# Camera.net
KiCad netlist of a schematic drawn in Altium Designer
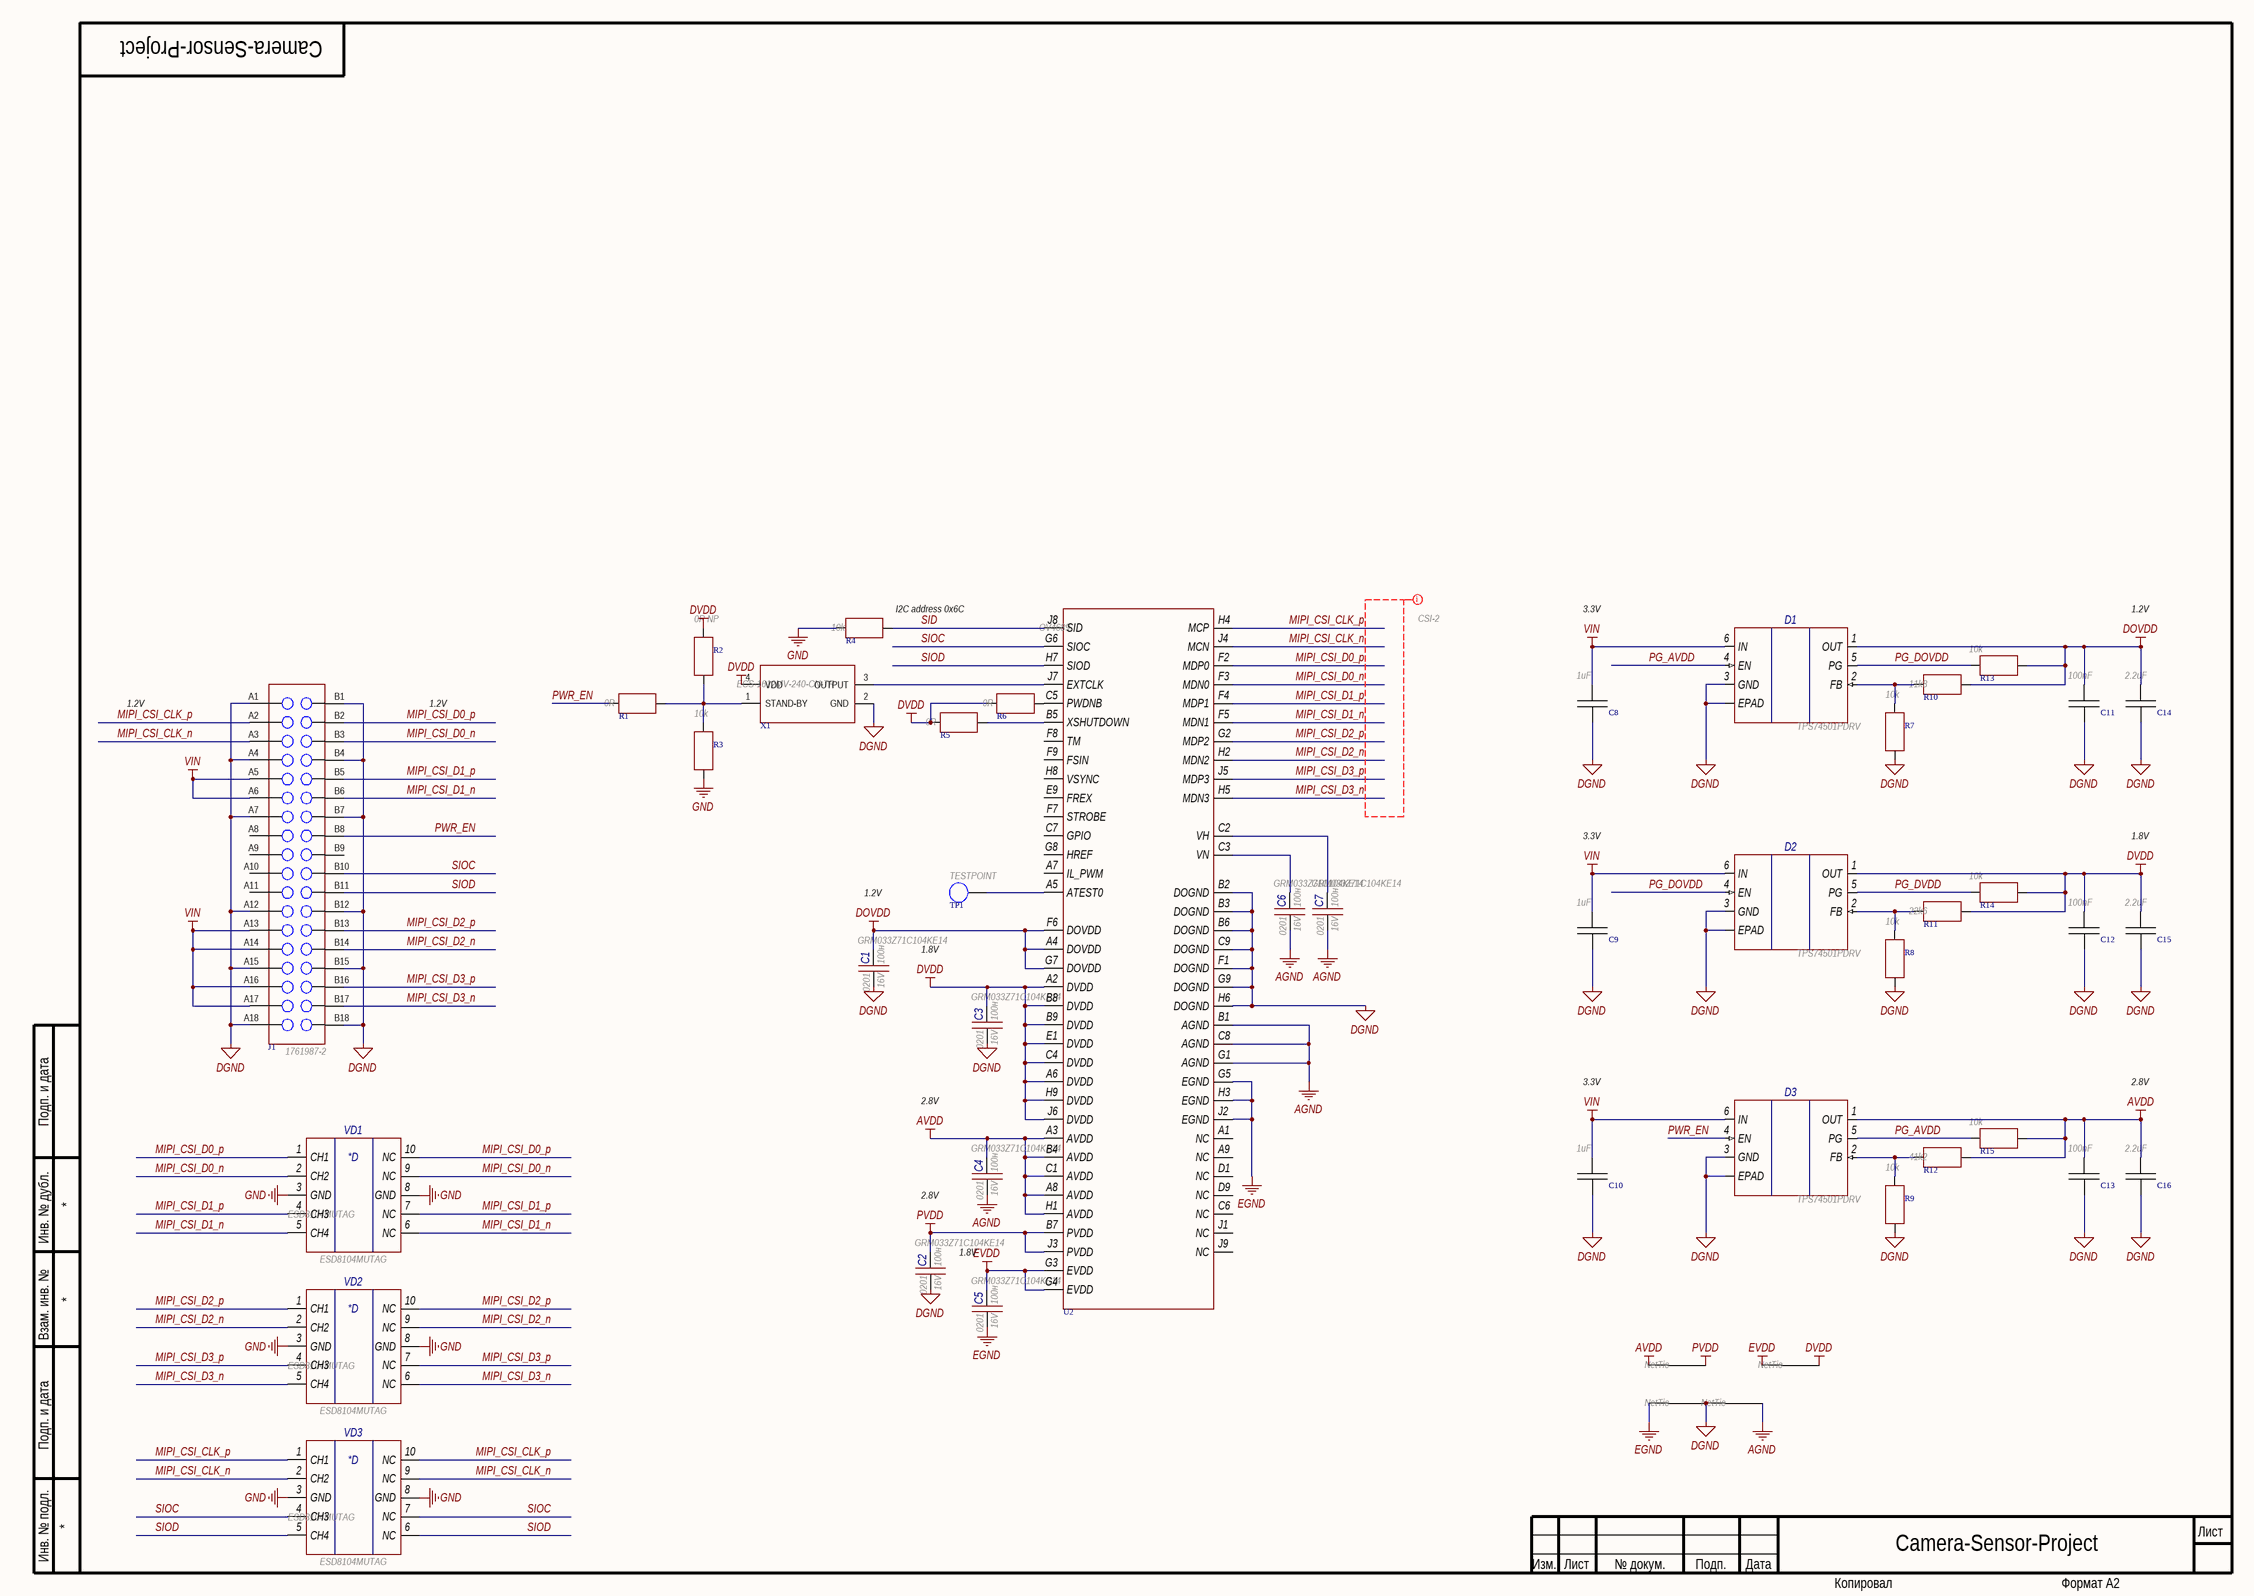
[diagram p0: Camera.SchDoc]

(export (version "E")
  (design (tool "Eeschema 10.0.6"))
  (components
    (comp (ref "C1")
      (value "GRM033Z71C104KE14")
      (footprint "CAPC_0.63x0.33x0.33Body; IPC: N; Pad Gap: 0.25")
      (fields
        (field (name "2) PACKAGE") "0201")
        (field (name "3) VOLTAGE") "16V")
        (field (name "ЗНАЧЕНИЕ") "100н")
        (field (name "MANUFACTURER") "Murata")
      )
      (libsource (lib "Concord PRO") (part "Capacitor Unpolarized"))
    )
    (comp (ref "C2")
      (value "GRM033Z71C104KE14")
      (footprint "CAPC_0.63x0.33x0.33Body; IPC: N; Pad Gap: 0.25")
      (fields
        (field (name "2) PACKAGE") "0201")
        (field (name "3) VOLTAGE") "16V")
        (field (name "ЗНАЧЕНИЕ") "100н")
        (field (name "MANUFACTURER") "Murata")
      )
      (libsource (lib "Concord PRO") (part "Capacitor Unpolarized"))
    )
    (comp (ref "C3")
      (value "GRM033Z71C104KE14")
      (footprint "CAPC_0.63x0.33x0.33Body; IPC: N; Pad Gap: 0.25")
      (fields
        (field (name "2) PACKAGE") "0201")
        (field (name "3) VOLTAGE") "16V")
        (field (name "ЗНАЧЕНИЕ") "100н")
        (field (name "MANUFACTURER") "Murata")
      )
      (libsource (lib "Concord PRO") (part "Capacitor Unpolarized"))
    )
    (comp (ref "C4")
      (value "GRM033Z71C104KE14")
      (footprint "CAPC_0.63x0.33x0.33Body; IPC: N; Pad Gap: 0.25")
      (fields
        (field (name "2) PACKAGE") "0201")
        (field (name "3) VOLTAGE") "16V")
        (field (name "ЗНАЧЕНИЕ") "100н")
        (field (name "MANUFACTURER") "Murata")
      )
      (libsource (lib "Concord PRO") (part "Capacitor Unpolarized"))
    )
    (comp (ref "C5")
      (value "GRM033Z71C104KE14")
      (footprint "CAPC_0.63x0.33x0.33Body; IPC: N; Pad Gap: 0.25")
      (fields
        (field (name "2) PACKAGE") "0201")
        (field (name "3) VOLTAGE") "16V")
        (field (name "ЗНАЧЕНИЕ") "100н")
        (field (name "MANUFACTURER") "Murata")
      )
      (libsource (lib "Concord PRO") (part "Capacitor Unpolarized"))
    )
    (comp (ref "C6")
      (value "GRM033Z71C104KE14")
      (footprint "CAPC_0.63x0.33x0.33Body; IPC: N; Pad Gap: 0.25")
      (fields
        (field (name "2) PACKAGE") "0201")
        (field (name "3) VOLTAGE") "16V")
        (field (name "ЗНАЧЕНИЕ") "100н")
        (field (name "MANUFACTURER") "Murata")
      )
      (libsource (lib "Concord PRO") (part "Capacitor Unpolarized"))
    )
    (comp (ref "C7")
      (value "GRM033Z71C104KE14")
      (footprint "CAPC_0.63x0.33x0.33Body; IPC: N; Pad Gap: 0.25")
      (fields
        (field (name "2) PACKAGE") "0201")
        (field (name "3) VOLTAGE") "16V")
        (field (name "ЗНАЧЕНИЕ") "100н")
        (field (name "MANUFACTURER") "Murata")
      )
      (libsource (lib "Concord PRO") (part "Capacitor Unpolarized"))
    )
    (comp (ref "C8")
      (value "1uF")
      (footprint "PcbLib:C0603")
      (fields
        (field (name "PART NUMBER") "CL10B105KO8NNNC")
        (field (name "TOLERANCE") "10%")
        (field (name "VOLTAGE") "16V")
      )
      (libsource (lib "Capacitor") (part "Cap 1uF 10% 16V_Samsung"))
    )
    (comp (ref "C9")
      (value "1uF")
      (footprint "PcbLib:C0603")
      (fields
        (field (name "PART NUMBER") "CL10B105KO8NNNC")
        (field (name "TOLERANCE") "10%")
        (field (name "VOLTAGE") "16V")
      )
      (libsource (lib "Capacitor") (part "Cap 1uF 10% 16V_Samsung"))
    )
    (comp (ref "C10")
      (value "1uF")
      (footprint "PcbLib:C0603")
      (fields
        (field (name "PART NUMBER") "CL10B105KO8NNNC")
        (field (name "TOLERANCE") "10%")
        (field (name "VOLTAGE") "16V")
      )
      (libsource (lib "Capacitor") (part "Cap 1uF 10% 16V_Samsung"))
    )
    (comp (ref "C11")
      (value "100nF")
      (footprint "PcbLib:C0603")
      (fields
        (field (name "PART NUMBER") "06033G104ZAT2A")
        (field (name "TOLERANCE") "+80% -20%")
        (field (name "VOLTAGE") "25V")
      )
      (libsource (lib "Capacitor") (part "Cap 100nF 20% 25V"))
    )
    (comp (ref "C12")
      (value "100nF")
      (footprint "PcbLib:C0603")
      (fields
        (field (name "PART NUMBER") "06033G104ZAT2A")
        (field (name "TOLERANCE") "+80% -20%")
        (field (name "VOLTAGE") "25V")
      )
      (libsource (lib "Capacitor") (part "Cap 100nF 20% 25V"))
    )
    (comp (ref "C13")
      (value "100nF")
      (footprint "PcbLib:C0603")
      (fields
        (field (name "PART NUMBER") "06033G104ZAT2A")
        (field (name "TOLERANCE") "+80% -20%")
        (field (name "VOLTAGE") "25V")
      )
      (libsource (lib "Capacitor") (part "Cap 100nF 20% 25V"))
    )
    (comp (ref "C14")
      (value "2.2uF")
      (footprint "PcbLib:C0603")
      (fields
        (field (name "PART NUMBER") "06036D225KAT2A")
        (field (name "TOLERANCE") "10%")
        (field (name "VOLTAGE") "6.3V")
      )
      (libsource (lib "Capacitor") (part "Cap 2.2uF 10% 6.3V"))
    )
    (comp (ref "C15")
      (value "2.2uF")
      (footprint "PcbLib:C0603")
      (fields
        (field (name "PART NUMBER") "06036D225KAT2A")
        (field (name "TOLERANCE") "10%")
        (field (name "VOLTAGE") "6.3V")
      )
      (libsource (lib "Capacitor") (part "Cap 2.2uF 10% 6.3V"))
    )
    (comp (ref "C16")
      (value "2.2uF")
      (footprint "PcbLib:C0603")
      (fields
        (field (name "PART NUMBER") "06036D225KAT2A")
        (field (name "TOLERANCE") "10%")
        (field (name "VOLTAGE") "6.3V")
      )
      (libsource (lib "Capacitor") (part "Cap 2.2uF 10% 6.3V"))
    )
    (comp (ref "D1")
      (value "TPS74501PDRV")
      (footprint "WSON6_2.1x2.1x0.8Body; Recommended: Texas Instruments")
      (description "IC REG LIN POS ADJ 500MA 6WSON")
      (fields (field (name "MANUFACTURER") "Texas Instruments"))
      (libsource (lib "Concord PRO") (part "TPS74501PDRV"))
    )
    (comp (ref "D2")
      (value "TPS74501PDRV")
      (footprint "WSON6_2.1x2.1x0.8Body; Recommended: Texas Instruments")
      (description "IC REG LIN POS ADJ 500MA 6WSON")
      (fields (field (name "MANUFACTURER") "Texas Instruments"))
      (libsource (lib "Concord PRO") (part "TPS74501PDRV"))
    )
    (comp (ref "D3")
      (value "TPS74501PDRV")
      (footprint "WSON6_2.1x2.1x0.8Body; Recommended: Texas Instruments")
      (description "IC REG LIN POS ADJ 500MA 6WSON")
      (fields (field (name "MANUFACTURER") "Texas Instruments"))
      (libsource (lib "Concord PRO") (part "TPS74501PDRV"))
    )
    (comp (ref "J1")
      (value "1761987-2")
      (footprint "CON: 36_1761987-2_TEC")
      (description "CONN MINI SAS RCP 36P SLD RA SMD")
      (libsource (lib "Connector") (part "1761987-2"))
    )
    (comp (ref "JT1")
      (value "NetTie")
      (footprint "CON: nettie_0.8")
      (libsource (lib "Other") (part "NetTie"))
    )
    (comp (ref "JT2")
      (value "NetTie")
      (footprint "CON: nettie_0.8")
      (libsource (lib "Other") (part "NetTie"))
    )
    (comp (ref "JT3")
      (value "NetTie")
      (footprint "CON: nettie_0.8")
      (libsource (lib "Other") (part "NetTie"))
    )
    (comp (ref "JT4")
      (value "NetTie")
      (footprint "CON: nettie_0.8")
      (libsource (lib "Other") (part "NetTie"))
    )
    (comp (ref "R1")
      (value "0R")
      (footprint "PcbLib:R0603")
      (fields (field (name "PART NUMBER") "P0.0GDKR-ND") (field (name "TOLERANCE") "5%"))
      (libsource (lib "Resistor") (part "Res 0R OHM 0603"))
    )
    (comp (ref "R2")
      (value "0R NP")
      (footprint "PcbLib:R0603")
      (fields (field (name "TOLERANCE") "1%"))
      (libsource (lib "Resistor") (part "Res 0R NP 1% 0603"))
    )
    (comp (ref "R3")
      (value "10k")
      (footprint "PcbLib:R0603")
      (fields (field (name "PART NUMBER") "P10.0KHTR-ND") (field (name "TOLERANCE") "1%"))
      (libsource (lib "Resistor") (part "Res 10k 1% 0603"))
    )
    (comp (ref "R4")
      (value "10k")
      (footprint "PcbLib:R0603")
      (fields (field (name "PART NUMBER") "P10.0KHTR-ND") (field (name "TOLERANCE") "1%"))
      (libsource (lib "") (part "Res 10k 1% 0603_2"))
    )
    (comp (ref "R5")
      (value "0R")
      (footprint "PcbLib:R0603")
      (fields (field (name "PART NUMBER") "P0.0GDKR-ND") (field (name "TOLERANCE") "5%"))
      (libsource (lib "Resistor") (part "Res 0R OHM 0603"))
    )
    (comp (ref "R6")
      (value "0R")
      (footprint "PcbLib:R0603")
      (fields (field (name "PART NUMBER") "P0.0GDKR-ND") (field (name "TOLERANCE") "5%"))
      (libsource (lib "Resistor") (part "Res 0R OHM 0603"))
    )
    (comp (ref "R7")
      (value "10k")
      (footprint "PcbLib:R0603")
      (fields (field (name "PART NUMBER") "P10.0KHTR-ND") (field (name "TOLERANCE") "1%"))
      (libsource (lib "Resistor") (part "Res 10k 1% 0603"))
    )
    (comp (ref "R8")
      (value "10k")
      (footprint "PcbLib:R0603")
      (fields (field (name "PART NUMBER") "P10.0KHTR-ND") (field (name "TOLERANCE") "1%"))
      (libsource (lib "Resistor") (part "Res 10k 1% 0603"))
    )
    (comp (ref "R9")
      (value "10k")
      (footprint "PcbLib:R0603")
      (fields (field (name "PART NUMBER") "P10.0KHTR-ND") (field (name "TOLERANCE") "1%"))
      (libsource (lib "Resistor") (part "Res 10k 1% 0603"))
    )
    (comp (ref "R10")
      (value "11k8")
      (footprint "PcbLib:R0603")
      (fields (field (name "TOLERANCE") "1%"))
      (libsource (lib "Resistor") (part "Res 11k8 1% 0603"))
    )
    (comp (ref "R11")
      (value "22k6")
      (footprint "PcbLib:R0603")
      (fields (field (name "TOLERANCE") "1%"))
      (libsource (lib "Resistor") (part "Res 22k6 1% 0603"))
    )
    (comp (ref "R12")
      (value "41k2")
      (footprint "PcbLib:R0603")
      (fields (field (name "TOLERANCE") "1%"))
      (libsource (lib "Resistor") (part "Res 41k2 1% 0603"))
    )
    (comp (ref "R13")
      (value "10k")
      (footprint "PcbLib:R0603")
      (fields (field (name "PART NUMBER") "P10.0KHTR-ND") (field (name "TOLERANCE") "1%"))
      (libsource (lib "") (part "Res 10k 1% 0603_1"))
    )
    (comp (ref "R14")
      (value "10k")
      (footprint "PcbLib:R0603")
      (fields (field (name "PART NUMBER") "P10.0KHTR-ND") (field (name "TOLERANCE") "1%"))
      (libsource (lib "") (part "Res 10k 1% 0603_1"))
    )
    (comp (ref "R15")
      (value "10k")
      (footprint "PcbLib:R0603")
      (fields (field (name "PART NUMBER") "P10.0KHTR-ND") (field (name "TOLERANCE") "1%"))
      (libsource (lib "") (part "Res 10k 1% 0603_1"))
    )
    (comp (ref "TP1")
      (value "TESTPOINT")
      (footprint "PcbLib:TP")
      (libsource (lib "Other") (part "TESTPOINT"))
    )
    (comp (ref "U2")
      (value "OV4689")
      (footprint "81-BGA-OMNIVISION4669")
      (description "IMAGE SENSOR 4MP 1/3 CIS SO81-BGA")
      (libsource (lib "IC") (part "OV4689"))
    )
    (comp (ref "VD1")
      (value "ESD8104MUTAG")
      (footprint "UDFN10_1.0x2.5x0.55Body; Recommended: onsemi")
      (fields (field (name "PART NUMBER") "ESD8104MUTAG") (field (name "MANUFACTURER") "onsemi"))
      (libsource (lib "Concord PRO") (part "TVS; Unidirectional Channels{colon} 4; Pinout{colon} 1, 2, 4, 5 - channels, 3, 8 - GND, 6, 7, 9, 10 - NC"))
    )
    (comp (ref "VD2")
      (value "ESD8104MUTAG")
      (footprint "UDFN10_1.0x2.5x0.55Body; Recommended: onsemi")
      (fields (field (name "PART NUMBER") "ESD8104MUTAG") (field (name "MANUFACTURER") "onsemi"))
      (libsource (lib "Concord PRO") (part "TVS; Unidirectional Channels{colon} 4; Pinout{colon} 1, 2, 4, 5 - channels, 3, 8 - GND, 6, 7, 9, 10 - NC"))
    )
    (comp (ref "VD3")
      (value "ESD8104MUTAG")
      (footprint "UDFN10_1.0x2.5x0.55Body; Recommended: onsemi")
      (fields (field (name "PART NUMBER") "ESD8104MUTAG") (field (name "MANUFACTURER") "onsemi"))
      (libsource (lib "Concord PRO") (part "TVS; Unidirectional Channels{colon} 4; Pinout{colon} 1, 2, 4, 5 - channels, 3, 8 - GND, 6, 7, 9, 10 - NC"))
    )
    (comp (ref "X1")
      (value "ECS-1612MV-240-CN-TR")
      (footprint "DFN1.6X1.2")
      (description "XTAL OSC XO 24.0000MHZ CMOS SMD")
      (libsource (lib "Synchronization") (part "ECS-1612MV-240-CN-TR"))
    )
  )
  (nets
    (net (code "1") (name "/MIPI_CSI_CLK_n") (class "Default")
      (node (ref "J1") (pin "A3") (pinfunction "A3_A3") (pintype "passive"))
      (node (ref "U2") (pin "J4") (pinfunction "MCN_J4") (pintype "passive"))
      (node (ref "VD3") (pin "2") (pinfunction "CH2_2") (pintype "passive"))
      (node (ref "VD3") (pin "9") (pinfunction "NC_9") (pintype "passive"))
    )
    (net (code "2") (name "/MIPI_CSI_CLK_p") (class "Default")
      (node (ref "J1") (pin "A2") (pinfunction "A2_A2") (pintype "passive"))
      (node (ref "U2") (pin "H4") (pinfunction "MCP_H4") (pintype "passive"))
      (node (ref "VD3") (pin "1") (pinfunction "CH1_1") (pintype "passive"))
      (node (ref "VD3") (pin "10") (pinfunction "NC_10") (pintype "passive"))
    )
    (net (code "3") (name "/MIPI_CSI_D0_n") (class "Default")
      (node (ref "J1") (pin "B3") (pinfunction "B3_B3") (pintype "passive"))
      (node (ref "U2") (pin "F3") (pinfunction "MDN0_F3") (pintype "passive"))
      (node (ref "VD1") (pin "2") (pinfunction "CH2_2") (pintype "passive"))
      (node (ref "VD1") (pin "9") (pinfunction "NC_9") (pintype "passive"))
    )
    (net (code "4") (name "/MIPI_CSI_D0_p") (class "Default")
      (node (ref "J1") (pin "B2") (pinfunction "B2_B2") (pintype "passive"))
      (node (ref "U2") (pin "F2") (pinfunction "MDP0_F2") (pintype "passive"))
      (node (ref "VD1") (pin "1") (pinfunction "CH1_1") (pintype "passive"))
      (node (ref "VD1") (pin "10") (pinfunction "NC_10") (pintype "passive"))
    )
    (net (code "5") (name "/MIPI_CSI_D1_n") (class "Default")
      (node (ref "J1") (pin "B6") (pinfunction "B6_B6") (pintype "passive"))
      (node (ref "U2") (pin "F5") (pinfunction "MDN1_F5") (pintype "passive"))
      (node (ref "VD1") (pin "5") (pinfunction "CH4_5") (pintype "passive"))
      (node (ref "VD1") (pin "6") (pinfunction "NC_6") (pintype "passive"))
    )
    (net (code "6") (name "/MIPI_CSI_D1_p") (class "Default")
      (node (ref "J1") (pin "B5") (pinfunction "B5_B5") (pintype "passive"))
      (node (ref "U2") (pin "F4") (pinfunction "MDP1_F4") (pintype "passive"))
      (node (ref "VD1") (pin "4") (pinfunction "CH3_4") (pintype "passive"))
      (node (ref "VD1") (pin "7") (pinfunction "NC_7") (pintype "passive"))
    )
    (net (code "7") (name "/MIPI_CSI_D2_n") (class "Default")
      (node (ref "J1") (pin "B14") (pinfunction "B14_B14") (pintype "passive"))
      (node (ref "U2") (pin "H2") (pinfunction "MDN2_H2") (pintype "passive"))
      (node (ref "VD2") (pin "2") (pinfunction "CH2_2") (pintype "passive"))
      (node (ref "VD2") (pin "9") (pinfunction "NC_9") (pintype "passive"))
    )
    (net (code "8") (name "/MIPI_CSI_D2_p") (class "Default")
      (node (ref "J1") (pin "B13") (pinfunction "B13_B13") (pintype "passive"))
      (node (ref "U2") (pin "G2") (pinfunction "MDP2_G2") (pintype "passive"))
      (node (ref "VD2") (pin "1") (pinfunction "CH1_1") (pintype "passive"))
      (node (ref "VD2") (pin "10") (pinfunction "NC_10") (pintype "passive"))
    )
    (net (code "9") (name "/MIPI_CSI_D3_n") (class "Default")
      (node (ref "J1") (pin "B17") (pinfunction "B17_B17") (pintype "passive"))
      (node (ref "U2") (pin "H5") (pinfunction "MDN3_H5") (pintype "passive"))
      (node (ref "VD2") (pin "5") (pinfunction "CH4_5") (pintype "passive"))
      (node (ref "VD2") (pin "6") (pinfunction "NC_6") (pintype "passive"))
    )
    (net (code "10") (name "/MIPI_CSI_D3_p") (class "Default")
      (node (ref "J1") (pin "B16") (pinfunction "B16_B16") (pintype "passive"))
      (node (ref "U2") (pin "J5") (pinfunction "MDP3_J5") (pintype "passive"))
      (node (ref "VD2") (pin "4") (pinfunction "CH3_4") (pintype "passive"))
      (node (ref "VD2") (pin "7") (pinfunction "NC_7") (pintype "passive"))
    )
    (net (code "11") (name "/PG_AVDD") (class "Default")
      (node (ref "D1") (pin "4") (pinfunction "EN_4") (pintype "input"))
      (node (ref "D3") (pin "5") (pinfunction "PG_5") (pintype "open_collector"))
      (node (ref "R15") (pin "2") (pintype "power_in"))
    )
    (net (code "12") (name "/PG_DOVDD") (class "Default")
      (node (ref "D1") (pin "5") (pinfunction "PG_5") (pintype "open_collector"))
      (node (ref "D2") (pin "4") (pinfunction "EN_4") (pintype "input"))
      (node (ref "R13") (pin "2") (pintype "power_in"))
    )
    (net (code "13") (name "/PG_DVDD") (class "Default")
      (node (ref "D2") (pin "5") (pinfunction "PG_5") (pintype "open_collector"))
      (node (ref "R14") (pin "2") (pintype "power_in"))
    )
    (net (code "14") (name "/PWR_EN") (class "Default")
      (node (ref "D3") (pin "4") (pinfunction "EN_4") (pintype "input"))
      (node (ref "J1") (pin "B8") (pinfunction "B8_B8") (pintype "passive"))
      (node (ref "R1") (pin "1") (pintype "power_in"))
    )
    (net (code "15") (name "/SID") (class "Default")
      (node (ref "R4") (pin "2") (pintype "power_in"))
      (node (ref "U2") (pin "J8") (pinfunction "SID_J8") (pintype "passive"))
    )
    (net (code "16") (name "/SIOC") (class "Default")
      (node (ref "J1") (pin "B10") (pinfunction "B10_B10") (pintype "passive"))
      (node (ref "U2") (pin "G6") (pinfunction "SIOC_G6") (pintype "passive"))
      (node (ref "VD3") (pin "4") (pinfunction "CH3_4") (pintype "passive"))
      (node (ref "VD3") (pin "7") (pinfunction "NC_7") (pintype "passive"))
    )
    (net (code "17") (name "/SIOD") (class "Default")
      (node (ref "J1") (pin "B11") (pinfunction "B11_B11") (pintype "passive"))
      (node (ref "U2") (pin "H7") (pinfunction "SIOD_H7") (pintype "passive"))
      (node (ref "VD3") (pin "5") (pinfunction "CH4_5") (pintype "passive"))
      (node (ref "VD3") (pin "6") (pinfunction "NC_6") (pintype "passive"))
    )
    (net (code "18") (name "AGND") (class "Default")
      (node (ref "C4") (pin "1") (pinfunction "1_1") (pintype "passive"))
      (node (ref "C6") (pin "1") (pinfunction "1_1") (pintype "passive"))
      (node (ref "C7") (pin "1") (pinfunction "1_1") (pintype "passive"))
      (node (ref "JT3") (pin "2") (pinfunction "2_2") (pintype "passive"))
      (node (ref "U2") (pin "B1") (pinfunction "AGND_B1") (pintype "passive"))
      (node (ref "U2") (pin "C8") (pinfunction "AGND_C8") (pintype "passive"))
      (node (ref "U2") (pin "G1") (pinfunction "AGND_G1") (pintype "passive"))
    )
    (net (code "19") (name "AVDD") (class "Default")
      (node (ref "C13") (pin "2") (pintype "power_in"))
      (node (ref "C16") (pin "2") (pintype "power_in"))
      (node (ref "C4") (pin "2") (pinfunction "2_2") (pintype "passive"))
      (node (ref "D3") (pin "1") (pinfunction "OUT_1") (pintype "power_in"))
      (node (ref "JT1") (pin "1") (pinfunction "1_1") (pintype "passive"))
      (node (ref "R12") (pin "2") (pintype "power_in"))
      (node (ref "R15") (pin "1") (pintype "power_in"))
      (node (ref "U2") (pin "A3") (pinfunction "AVDD_A3") (pintype "passive"))
      (node (ref "U2") (pin "A8") (pinfunction "AVDD_A8") (pintype "passive"))
      (node (ref "U2") (pin "B4") (pinfunction "AVDD_B4") (pintype "passive"))
      (node (ref "U2") (pin "C1") (pinfunction "AVDD_C1") (pintype "passive"))
      (node (ref "U2") (pin "H1") (pinfunction "AVDD_H1") (pintype "passive"))
    )
    (net (code "20") (name "DGND") (class "Default")
      (node (ref "C1") (pin "1") (pinfunction "1_1") (pintype "passive"))
      (node (ref "C10") (pin "1") (pintype "power_in"))
      (node (ref "C11") (pin "1") (pintype "power_in"))
      (node (ref "C12") (pin "1") (pintype "power_in"))
      (node (ref "C13") (pin "1") (pintype "power_in"))
      (node (ref "C14") (pin "1") (pintype "power_in"))
      (node (ref "C15") (pin "1") (pintype "power_in"))
      (node (ref "C16") (pin "1") (pintype "power_in"))
      (node (ref "C2") (pin "1") (pinfunction "1_1") (pintype "passive"))
      (node (ref "C3") (pin "1") (pinfunction "1_1") (pintype "passive"))
      (node (ref "C8") (pin "1") (pintype "power_in"))
      (node (ref "C9") (pin "1") (pintype "power_in"))
      (node (ref "D1") (pin "3") (pinfunction "GND_3") (pintype "power_in"))
      (node (ref "D1") (pin "EPAD") (pinfunction "EPAD_EPAD") (pintype "power_in"))
      (node (ref "D2") (pin "3") (pinfunction "GND_3") (pintype "power_in"))
      (node (ref "D2") (pin "EPAD") (pinfunction "EPAD_EPAD") (pintype "power_in"))
      (node (ref "D3") (pin "3") (pinfunction "GND_3") (pintype "power_in"))
      (node (ref "D3") (pin "EPAD") (pinfunction "EPAD_EPAD") (pintype "power_in"))
      (node (ref "J1") (pin "A1") (pinfunction "A1_A1") (pintype "passive"))
      (node (ref "J1") (pin "A12") (pinfunction "A12_A12") (pintype "passive"))
      (node (ref "J1") (pin "A15") (pinfunction "A15_A15") (pintype "passive"))
      (node (ref "J1") (pin "A18") (pinfunction "A18_A18") (pintype "passive"))
      (node (ref "J1") (pin "A4") (pinfunction "A4_A4") (pintype "passive"))
      (node (ref "J1") (pin "A7") (pinfunction "A7_A7") (pintype "passive"))
      (node (ref "J1") (pin "B1") (pinfunction "B1_B1") (pintype "passive"))
      (node (ref "J1") (pin "B12") (pinfunction "B12_B12") (pintype "passive"))
      (node (ref "J1") (pin "B15") (pinfunction "B15_B15") (pintype "passive"))
      (node (ref "J1") (pin "B18") (pinfunction "B18_B18") (pintype "passive"))
      (node (ref "J1") (pin "B4") (pinfunction "B4_B4") (pintype "passive"))
      (node (ref "J1") (pin "B7") (pinfunction "B7_B7") (pintype "passive"))
      (node (ref "JT2") (pin "2") (pinfunction "2_2") (pintype "passive"))
      (node (ref "JT3") (pin "1") (pinfunction "1_1") (pintype "passive"))
      (node (ref "R7") (pin "1") (pintype "power_in"))
      (node (ref "R8") (pin "1") (pintype "power_in"))
      (node (ref "R9") (pin "1") (pintype "power_in"))
      (node (ref "U2") (pin "B2") (pinfunction "DOGND_B2") (pintype "passive"))
      (node (ref "U2") (pin "B3") (pinfunction "DOGND_B3") (pintype "passive"))
      (node (ref "U2") (pin "B6") (pinfunction "DOGND_B6") (pintype "passive"))
      (node (ref "U2") (pin "C9") (pinfunction "DOGND_C9") (pintype "passive"))
      (node (ref "U2") (pin "F1") (pinfunction "DOGND_F1") (pintype "passive"))
      (node (ref "U2") (pin "G9") (pinfunction "DOGND_G9") (pintype "passive"))
      (node (ref "U2") (pin "H6") (pinfunction "DOGND_H6") (pintype "passive"))
      (node (ref "X1") (pin "2") (pinfunction "GND_2") (pintype "passive"))
    )
    (net (code "21") (name "DOVDD") (class "Default")
      (node (ref "C1") (pin "2") (pinfunction "2_2") (pintype "passive"))
      (node (ref "C11") (pin "2") (pintype "power_in"))
      (node (ref "C14") (pin "2") (pintype "power_in"))
      (node (ref "D1") (pin "1") (pinfunction "OUT_1") (pintype "power_in"))
      (node (ref "R10") (pin "2") (pintype "power_in"))
      (node (ref "R13") (pin "1") (pintype "power_in"))
      (node (ref "U2") (pin "A4") (pinfunction "DOVDD_A4") (pintype "passive"))
      (node (ref "U2") (pin "F6") (pinfunction "DOVDD_F6") (pintype "passive"))
      (node (ref "U2") (pin "G7") (pinfunction "DOVDD_G7") (pintype "passive"))
    )
    (net (code "22") (name "DVDD") (class "Default")
      (node (ref "C12") (pin "2") (pintype "power_in"))
      (node (ref "C15") (pin "2") (pintype "power_in"))
      (node (ref "C3") (pin "2") (pinfunction "2_2") (pintype "passive"))
      (node (ref "D2") (pin "1") (pinfunction "OUT_1") (pintype "power_in"))
      (node (ref "JT4") (pin "2") (pinfunction "2_2") (pintype "passive"))
      (node (ref "R11") (pin "2") (pintype "power_in"))
      (node (ref "R14") (pin "1") (pintype "power_in"))
      (node (ref "R2") (pin "2") (pintype "power_in"))
      (node (ref "R5") (pin "1") (pintype "power_in"))
      (node (ref "R6") (pin "1") (pintype "power_in"))
      (node (ref "U2") (pin "A2") (pinfunction "DVDD_A2") (pintype "passive"))
      (node (ref "U2") (pin "A6") (pinfunction "DVDD_A6") (pintype "passive"))
      (node (ref "U2") (pin "B8") (pinfunction "DVDD_B8") (pintype "passive"))
      (node (ref "U2") (pin "B9") (pinfunction "DVDD_B9") (pintype "passive"))
      (node (ref "U2") (pin "C4") (pinfunction "DVDD_C4") (pintype "passive"))
      (node (ref "U2") (pin "E1") (pinfunction "DVDD_E1") (pintype "passive"))
      (node (ref "U2") (pin "H9") (pinfunction "DVDD_H9") (pintype "passive"))
      (node (ref "U2") (pin "J6") (pinfunction "DVDD_J6") (pintype "passive"))
      (node (ref "X1") (pin "4") (pinfunction "VDD_4") (pintype "passive"))
    )
    (net (code "23") (name "EGND") (class "Default")
      (node (ref "C5") (pin "1") (pinfunction "1_1") (pintype "passive"))
      (node (ref "JT2") (pin "1") (pinfunction "1_1") (pintype "passive"))
      (node (ref "U2") (pin "G5") (pinfunction "EGND_G5") (pintype "passive"))
      (node (ref "U2") (pin "H3") (pinfunction "EGND_H3") (pintype "passive"))
      (node (ref "U2") (pin "J2") (pinfunction "EGND_J2") (pintype "passive"))
    )
    (net (code "24") (name "EVDD") (class "Default")
      (node (ref "C5") (pin "2") (pinfunction "2_2") (pintype "passive"))
      (node (ref "JT4") (pin "1") (pinfunction "1_1") (pintype "passive"))
      (node (ref "U2") (pin "G3") (pinfunction "EVDD_G3") (pintype "passive"))
      (node (ref "U2") (pin "G4") (pinfunction "EVDD_G4") (pintype "passive"))
    )
    (net (code "25") (name "GND") (class "Default")
      (node (ref "R3") (pin "1") (pintype "power_in"))
      (node (ref "R4") (pin "1") (pintype "power_in"))
      (node (ref "VD1") (pin "3") (pinfunction "GND_3") (pintype "passive"))
      (node (ref "VD1") (pin "8") (pinfunction "GND_8") (pintype "passive"))
      (node (ref "VD2") (pin "3") (pinfunction "GND_3") (pintype "passive"))
      (node (ref "VD2") (pin "8") (pinfunction "GND_8") (pintype "passive"))
      (node (ref "VD3") (pin "3") (pinfunction "GND_3") (pintype "passive"))
      (node (ref "VD3") (pin "8") (pinfunction "GND_8") (pintype "passive"))
    )
    (net (code "26") (name "Net-(D1-FB)") (class "Default")
      (node (ref "D1") (pin "2") (pinfunction "FB_2") (pintype "input"))
      (node (ref "R10") (pin "1") (pintype "power_in"))
      (node (ref "R7") (pin "2") (pintype "power_in"))
    )
    (net (code "27") (name "Net-(D2-FB)") (class "Default")
      (node (ref "D2") (pin "2") (pinfunction "FB_2") (pintype "input"))
      (node (ref "R11") (pin "1") (pintype "power_in"))
      (node (ref "R8") (pin "2") (pintype "power_in"))
    )
    (net (code "28") (name "Net-(D3-FB)") (class "Default")
      (node (ref "D3") (pin "2") (pinfunction "FB_2") (pintype "input"))
      (node (ref "R12") (pin "1") (pintype "power_in"))
      (node (ref "R9") (pin "2") (pintype "power_in"))
    )
    (net (code "29") (name "Net-(U2-ATEST0)") (class "Default")
      (node (ref "TP1") (pin "1") (pinfunction "1_1") (pintype "passive"))
      (node (ref "U2") (pin "A5") (pinfunction "ATEST0_A5") (pintype "passive"))
    )
    (net (code "30") (name "Net-(U2-EXTCLK)") (class "Default")
      (node (ref "U2") (pin "J7") (pinfunction "EXTCLK_J7") (pintype "passive"))
      (node (ref "X1") (pin "3") (pinfunction "OUTPUT_3") (pintype "passive"))
    )
    (net (code "31") (name "Net-(U2-PWDNB)") (class "Default")
      (node (ref "R6") (pin "2") (pintype "power_in"))
      (node (ref "U2") (pin "C5") (pinfunction "PWDNB_C5") (pintype "passive"))
    )
    (net (code "32") (name "Net-(U2-VH)") (class "Default")
      (node (ref "C7") (pin "2") (pinfunction "2_2") (pintype "passive"))
      (node (ref "U2") (pin "C2") (pinfunction "VH_C2") (pintype "passive"))
    )
    (net (code "33") (name "Net-(U2-VN)") (class "Default")
      (node (ref "C6") (pin "2") (pinfunction "2_2") (pintype "passive"))
      (node (ref "U2") (pin "C3") (pinfunction "VN_C3") (pintype "passive"))
    )
    (net (code "34") (name "Net-(U2-XSHUTDOWN)") (class "Default")
      (node (ref "R5") (pin "2") (pintype "power_in"))
      (node (ref "U2") (pin "B5") (pinfunction "XSHUTDOWN_B5") (pintype "passive"))
    )
    (net (code "35") (name "Net-(X1-STAND-BY)") (class "Default")
      (node (ref "R1") (pin "2") (pintype "power_in"))
      (node (ref "R2") (pin "1") (pintype "power_in"))
      (node (ref "R3") (pin "2") (pintype "power_in"))
      (node (ref "X1") (pin "1") (pinfunction "STAND-BY_1") (pintype "passive"))
    )
    (net (code "36") (name "PVDD") (class "Default")
      (node (ref "C2") (pin "2") (pinfunction "2_2") (pintype "passive"))
      (node (ref "JT1") (pin "2") (pinfunction "2_2") (pintype "passive"))
      (node (ref "U2") (pin "B7") (pinfunction "PVDD_B7") (pintype "passive"))
      (node (ref "U2") (pin "J3") (pinfunction "PVDD_J3") (pintype "passive"))
    )
    (net (code "37") (name "VIN") (class "Default")
      (node (ref "C10") (pin "2") (pintype "power_in"))
      (node (ref "C8") (pin "2") (pintype "power_in"))
      (node (ref "C9") (pin "2") (pintype "power_in"))
      (node (ref "D1") (pin "6") (pinfunction "IN_6") (pintype "power_in"))
      (node (ref "D2") (pin "6") (pinfunction "IN_6") (pintype "power_in"))
      (node (ref "D3") (pin "6") (pinfunction "IN_6") (pintype "power_in"))
      (node (ref "J1") (pin "A13") (pinfunction "A13_A13") (pintype "passive"))
      (node (ref "J1") (pin "A14") (pinfunction "A14_A14") (pintype "passive"))
      (node (ref "J1") (pin "A16") (pinfunction "A16_A16") (pintype "passive"))
      (node (ref "J1") (pin "A17") (pinfunction "A17_A17") (pintype "passive"))
      (node (ref "J1") (pin "A5") (pinfunction "A5_A5") (pintype "passive"))
      (node (ref "J1") (pin "A6") (pinfunction "A6_A6") (pintype "passive"))
    )
    (net (code "38") (name "unconnected-(J1-PadA8)") (class "Default")
      (node (ref "J1") (pin "A8") (pinfunction "A8_A8") (pintype "passive"))
    )
    (net (code "39") (name "unconnected-(J1-PadA9)") (class "Default")
      (node (ref "J1") (pin "A9") (pinfunction "A9_A9") (pintype "passive"))
    )
    (net (code "40") (name "unconnected-(J1-PadA10)") (class "Default")
      (node (ref "J1") (pin "A10") (pinfunction "A10_A10") (pintype "passive"))
    )
    (net (code "41") (name "unconnected-(J1-PadA11)") (class "Default")
      (node (ref "J1") (pin "A11") (pinfunction "A11_A11") (pintype "passive"))
    )
    (net (code "42") (name "unconnected-(J1-PadB9)") (class "Default")
      (node (ref "J1") (pin "B9") (pinfunction "B9_B9") (pintype "passive"))
    )
    (net (code "43") (name "unconnected-(U2-FREX-PadE9)") (class "Default")
      (node (ref "U2") (pin "E9") (pinfunction "FREX_E9") (pintype "passive"))
    )
    (net (code "44") (name "unconnected-(U2-FSIN-PadF9)") (class "Default")
      (node (ref "U2") (pin "F9") (pinfunction "FSIN_F9") (pintype "passive"))
    )
    (net (code "45") (name "unconnected-(U2-GPIO-PadC7)") (class "Default")
      (node (ref "U2") (pin "C7") (pinfunction "GPIO_C7") (pintype "passive"))
    )
    (net (code "46") (name "unconnected-(U2-HREF-PadG8)") (class "Default")
      (node (ref "U2") (pin "G8") (pinfunction "HREF_G8") (pintype "passive"))
    )
    (net (code "47") (name "unconnected-(U2-IL_PWM-PadA7)") (class "Default")
      (node (ref "U2") (pin "A7") (pinfunction "IL_PWM_A7") (pintype "passive"))
    )
    (net (code "48") (name "unconnected-(U2-NC-PadA1)") (class "Default")
      (node (ref "U2") (pin "A1") (pinfunction "NC_A1") (pintype "passive"))
    )
    (net (code "49") (name "unconnected-(U2-NC-PadA9)") (class "Default")
      (node (ref "U2") (pin "A9") (pinfunction "NC_A9") (pintype "passive"))
    )
    (net (code "50") (name "unconnected-(U2-NC-PadC6)") (class "Default")
      (node (ref "U2") (pin "C6") (pinfunction "NC_C6") (pintype "passive"))
    )
    (net (code "51") (name "unconnected-(U2-NC-PadD1)") (class "Default")
      (node (ref "U2") (pin "D1") (pinfunction "NC_D1") (pintype "passive"))
    )
    (net (code "52") (name "unconnected-(U2-NC-PadD9)") (class "Default")
      (node (ref "U2") (pin "D9") (pinfunction "NC_D9") (pintype "passive"))
    )
    (net (code "53") (name "unconnected-(U2-NC-PadJ1)") (class "Default")
      (node (ref "U2") (pin "J1") (pinfunction "NC_J1") (pintype "passive"))
    )
    (net (code "54") (name "unconnected-(U2-NC-PadJ9)") (class "Default")
      (node (ref "U2") (pin "J9") (pinfunction "NC_J9") (pintype "passive"))
    )
    (net (code "55") (name "unconnected-(U2-STROBE-PadF7)") (class "Default")
      (node (ref "U2") (pin "F7") (pinfunction "STROBE_F7") (pintype "passive"))
    )
    (net (code "56") (name "unconnected-(U2-TM-PadF8)") (class "Default")
      (node (ref "U2") (pin "F8") (pinfunction "TM_F8") (pintype "passive"))
    )
    (net (code "57") (name "unconnected-(U2-VSYNC-PadH8)") (class "Default")
      (node (ref "U2") (pin "H8") (pinfunction "VSYNC_H8") (pintype "passive"))
    )
  )
)
